# Syntheseproject.net
KiCad netlist of a schematic drawn in EasyEDA
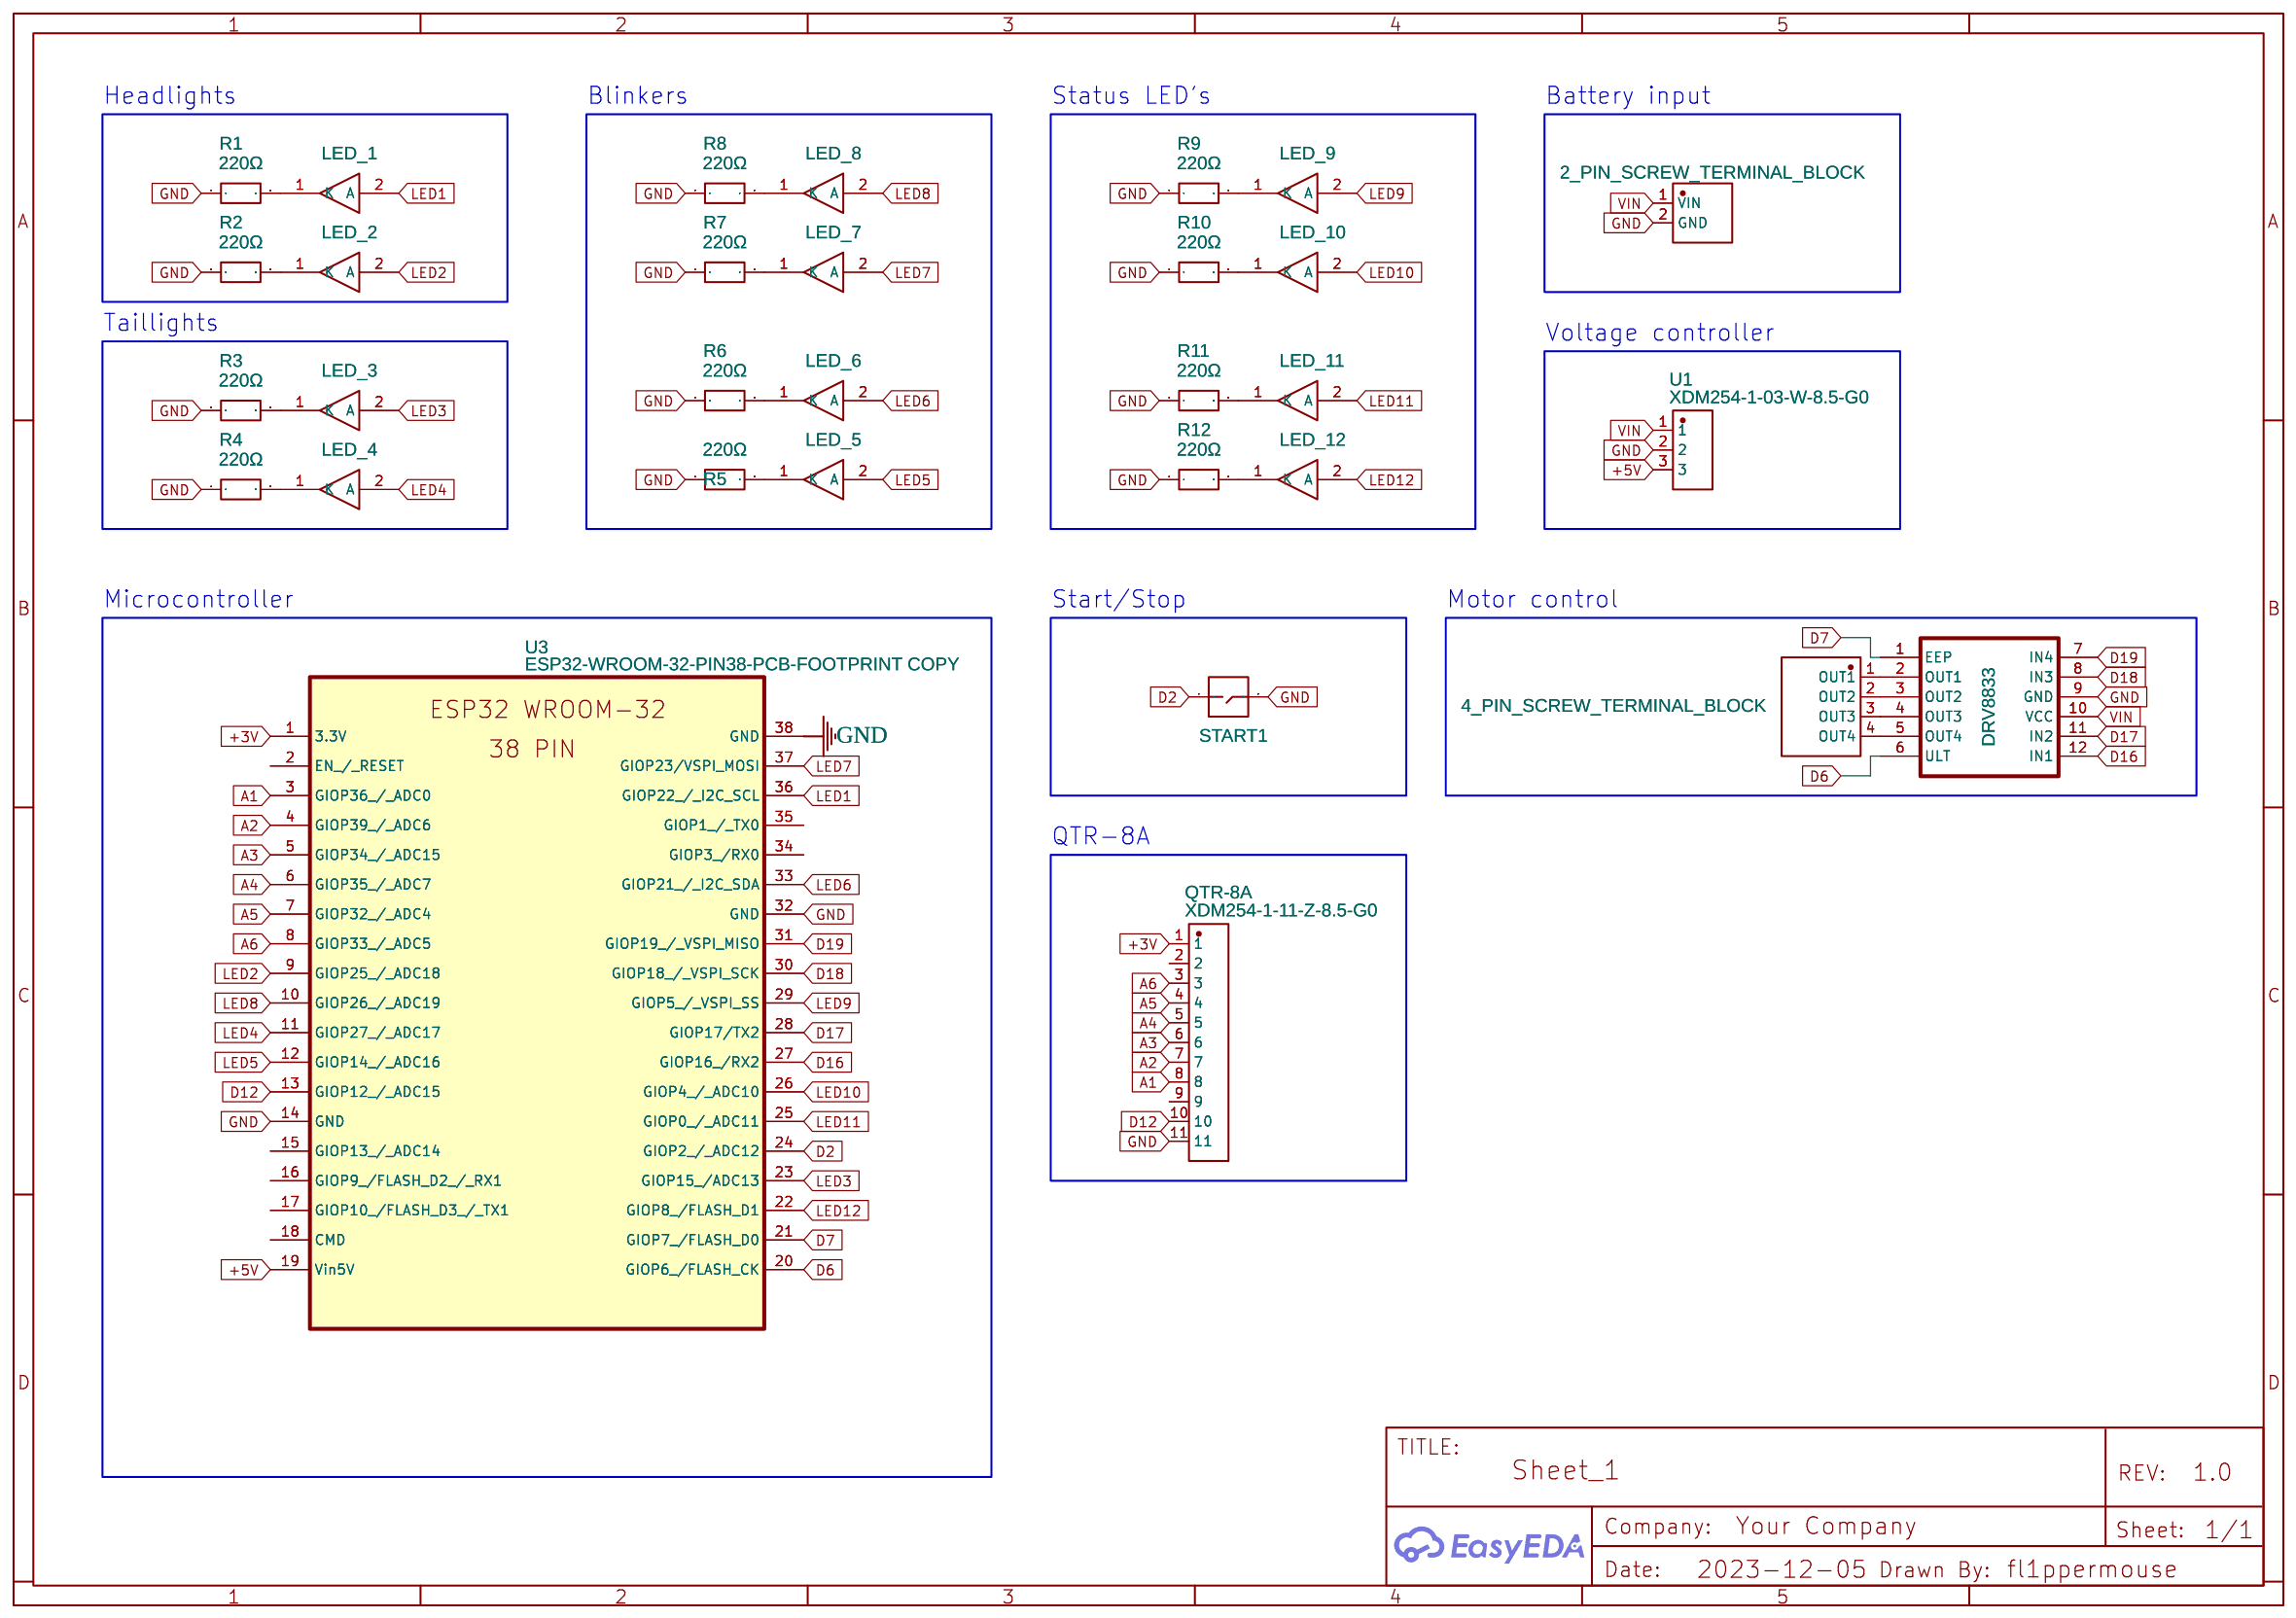
[diagram p0: schematic sheet]

(export (version "E")
  (design (tool "Eeschema 10.0.6"))
  (components
    (comp (ref "2_PIN_SCREW_TERMINAL_BLOCK")
      (value "2 Pin Screw Terminal Block Connector 2.54 mm")
      (libsource (lib "") (part "2 PIN SCREW TERMINAL BLOCK CONNECTOR 2.54 MM"))
    )
    (comp (ref "4_PIN_SCREW_TERMINAL_BLOCK")
      (value "4 PIN SCREW TERMINAL BLOCK CONNECTOR 2.54 MM")
      (libsource (lib "") (part "4 PIN SCREW TERMINAL BLOCK CONNECTOR 2.54 MM"))
    )
    (comp (ref "DRV8833") (value "DRV8833") (libsource (lib "") (part "DRV8833 12PIN")))
    (comp (ref "LED_1") (value "led 5 mm") (libsource (lib "") (part "led 5 mm")))
    (comp (ref "LED_2") (value "led 5 mm") (libsource (lib "") (part "led 5 mm")))
    (comp (ref "LED_3") (value "led 5 mm") (libsource (lib "") (part "led 5 mm")))
    (comp (ref "LED_4") (value "led 5 mm") (libsource (lib "") (part "led 5 mm")))
    (comp (ref "LED_5") (value "led 5 mm") (libsource (lib "") (part "led 5 mm")))
    (comp (ref "LED_6") (value "led 5 mm") (libsource (lib "") (part "led 5 mm")))
    (comp (ref "LED_7") (value "led 5 mm") (libsource (lib "") (part "led 5 mm")))
    (comp (ref "LED_8") (value "led 5 mm") (libsource (lib "") (part "led 5 mm")))
    (comp (ref "LED_9") (value "led 5 mm") (libsource (lib "") (part "led 5 mm")))
    (comp (ref "LED_10") (value "led 5 mm") (libsource (lib "") (part "led 5 mm")))
    (comp (ref "LED_11") (value "led 5 mm") (libsource (lib "") (part "led 5 mm")))
    (comp (ref "LED_12") (value "led 5 mm") (libsource (lib "") (part "led 5 mm")))
    (comp (ref "QTR-8A")
      (value "XDM254-1-11-Z-8.5-G0")
      (fields (field (name "Manufacturer") "XUNDA(讯答)"))
      (libsource (lib "") (part "XDM254-1-11-Z-8.5-G0"))
    )
    (comp (ref "R1")
      (value "220Ω")
      (libsource (lib "") (part "AXIAL RESISTOR 220 OHM - TH_BD2.3-L6.0-P10.00-D0.4"))
    )
    (comp (ref "R2")
      (value "220Ω")
      (libsource (lib "") (part "AXIAL RESISTOR 220 OHM - TH_BD2.3-L6.0-P10.00-D0.4"))
    )
    (comp (ref "R3")
      (value "220Ω")
      (libsource (lib "") (part "AXIAL RESISTOR 220 OHM - TH_BD2.3-L6.0-P10.00-D0.4"))
    )
    (comp (ref "R4")
      (value "220Ω")
      (libsource (lib "") (part "AXIAL RESISTOR 220 OHM - TH_BD2.3-L6.0-P10.00-D0.4"))
    )
    (comp (ref "R5")
      (value "220Ω")
      (libsource (lib "") (part "AXIAL RESISTOR 220 OHM - TH_BD2.3-L6.0-P10.00-D0.4"))
    )
    (comp (ref "R6")
      (value "220Ω")
      (libsource (lib "") (part "AXIAL RESISTOR 220 OHM - TH_BD2.3-L6.0-P10.00-D0.4"))
    )
    (comp (ref "R7")
      (value "220Ω")
      (libsource (lib "") (part "AXIAL RESISTOR 220 OHM - TH_BD2.3-L6.0-P10.00-D0.4"))
    )
    (comp (ref "R8")
      (value "220Ω")
      (libsource (lib "") (part "AXIAL RESISTOR 220 OHM - TH_BD2.3-L6.0-P10.00-D0.4"))
    )
    (comp (ref "R9")
      (value "220Ω")
      (libsource (lib "") (part "AXIAL RESISTOR 220 OHM - TH_BD2.3-L6.0-P10.00-D0.4"))
    )
    (comp (ref "R10")
      (value "220Ω")
      (libsource (lib "") (part "AXIAL RESISTOR 220 OHM - TH_BD2.3-L6.0-P10.00-D0.4"))
    )
    (comp (ref "R11")
      (value "220Ω")
      (libsource (lib "") (part "AXIAL RESISTOR 220 OHM - TH_BD2.3-L6.0-P10.00-D0.4"))
    )
    (comp (ref "R12")
      (value "220Ω")
      (libsource (lib "") (part "AXIAL RESISTOR 220 OHM - TH_BD2.3-L6.0-P10.00-D0.4"))
    )
    (comp (ref "START1") (value "start") (libsource (lib "") (part "Push Button")))
    (comp (ref "U1")
      (value "XDM254-1-03-W-8.5-G0")
      (fields (field (name "Manufacturer") "XUNDA(讯答)"))
      (libsource (lib "") (part "XDM254-1-03-W-8.5-G0"))
    )
    (comp (ref "U3")
      (value "ESP32-WROOM-32-PIN38-PCB-FOOTPRINT COPY")
      (fields
        (field (name "Manufacturer Part") "ESP32-WROOM-32")
        (field (name "Manufacturer") "Espressif Systems")
      )
      (libsource (lib "") (part "ESP32-WROOM-32-PIN38-PCB-FOOTPRINT COPY"))
    )
  )
  (nets
    (net (code "1") (name "+3V") (class "Default")
      (node (ref "QTR-8A") (pin "1") (pinfunction "1_1") (pintype "unspecified"))
      (node (ref "U3") (pin "1") (pinfunction "3.3V_1") (pintype "unspecified"))
    )
    (net (code "2") (name "+5V") (class "Default")
      (node (ref "U1") (pin "3") (pinfunction "3_3") (pintype "unspecified"))
      (node (ref "U3") (pin "19") (pinfunction "Vin5V_19") (pintype "unspecified"))
    )
    (net (code "3") (name "A1") (class "Default")
      (node (ref "QTR-8A") (pin "8") (pinfunction "8_8") (pintype "unspecified"))
      (node (ref "U3") (pin "3") (pinfunction "GIOP36_/_ADC0_3") (pintype "unspecified"))
    )
    (net (code "4") (name "A2") (class "Default")
      (node (ref "QTR-8A") (pin "7") (pinfunction "7_7") (pintype "unspecified"))
      (node (ref "U3") (pin "4") (pinfunction "GIOP39_/_ADC6_4") (pintype "unspecified"))
    )
    (net (code "5") (name "A3") (class "Default")
      (node (ref "QTR-8A") (pin "6") (pinfunction "6_6") (pintype "unspecified"))
      (node (ref "U3") (pin "5") (pinfunction "GIOP34_/_ADC15_5") (pintype "unspecified"))
    )
    (net (code "6") (name "A4") (class "Default")
      (node (ref "QTR-8A") (pin "5") (pinfunction "5_5") (pintype "unspecified"))
      (node (ref "U3") (pin "6") (pinfunction "GIOP35_/_ADC7_6") (pintype "unspecified"))
    )
    (net (code "7") (name "A5") (class "Default")
      (node (ref "QTR-8A") (pin "4") (pinfunction "4_4") (pintype "unspecified"))
      (node (ref "U3") (pin "7") (pinfunction "GIOP32_/_ADC4_7") (pintype "unspecified"))
    )
    (net (code "8") (name "A6") (class "Default")
      (node (ref "QTR-8A") (pin "3") (pinfunction "3_3") (pintype "unspecified"))
      (node (ref "U3") (pin "8") (pinfunction "GIOP33_/_ADC5_8") (pintype "unspecified"))
    )
    (net (code "9") (name "D2") (class "Default")
      (node (ref "START1") (pin "1") (pinfunction "1_1") (pintype "unspecified"))
      (node (ref "U3") (pin "24") (pinfunction "GIOP2_/_ADC12_24") (pintype "unspecified"))
    )
    (net (code "10") (name "D6") (class "Default")
      (node (ref "DRV8833") (pin "6") (pinfunction "ULT_6") (pintype "unspecified"))
      (node (ref "U3") (pin "20") (pinfunction "GIOP6_/FLASH_CK_20") (pintype "unspecified"))
    )
    (net (code "11") (name "D7") (class "Default")
      (node (ref "DRV8833") (pin "1") (pinfunction "EEP_1") (pintype "unspecified"))
      (node (ref "U3") (pin "21") (pinfunction "GIOP7_/FLASH_D0_21") (pintype "unspecified"))
    )
    (net (code "12") (name "D12") (class "Default")
      (node (ref "QTR-8A") (pin "10") (pinfunction "10_10") (pintype "unspecified"))
      (node (ref "U3") (pin "13") (pinfunction "GIOP12_/_ADC15_13") (pintype "unspecified"))
    )
    (net (code "13") (name "D16") (class "Default")
      (node (ref "DRV8833") (pin "12") (pinfunction "IN1_12") (pintype "unspecified"))
      (node (ref "U3") (pin "27") (pinfunction "GIOP16_/RX2_27") (pintype "unspecified"))
    )
    (net (code "14") (name "D17") (class "Default")
      (node (ref "DRV8833") (pin "11") (pinfunction "IN2_11") (pintype "unspecified"))
      (node (ref "U3") (pin "28") (pinfunction "GIOP17/TX2_28") (pintype "unspecified"))
    )
    (net (code "15") (name "D18") (class "Default")
      (node (ref "DRV8833") (pin "8") (pinfunction "IN3_8") (pintype "unspecified"))
      (node (ref "U3") (pin "30") (pinfunction "GIOP18_/_VSPI_SCK_30") (pintype "unspecified"))
    )
    (net (code "16") (name "D19") (class "Default")
      (node (ref "DRV8833") (pin "7") (pinfunction "IN4_7") (pintype "unspecified"))
      (node (ref "U3") (pin "31") (pinfunction "GIOP19_/_VSPI_MISO_31") (pintype "unspecified"))
    )
    (net (code "17") (name "GND") (class "Default")
      (node (ref "2_PIN_SCREW_TERMINAL_BLOCK") (pin "2") (pinfunction "GND_2") (pintype "unspecified"))
      (node (ref "DRV8833") (pin "9") (pinfunction "GND_9") (pintype "unspecified"))
      (node (ref "QTR-8A") (pin "11") (pinfunction "11_11") (pintype "unspecified"))
      (node (ref "R1") (pin "1") (pinfunction "1_1") (pintype "unspecified"))
      (node (ref "R10") (pin "1") (pinfunction "1_1") (pintype "unspecified"))
      (node (ref "R11") (pin "1") (pinfunction "1_1") (pintype "unspecified"))
      (node (ref "R12") (pin "1") (pinfunction "1_1") (pintype "unspecified"))
      (node (ref "R2") (pin "1") (pinfunction "1_1") (pintype "unspecified"))
      (node (ref "R3") (pin "1") (pinfunction "1_1") (pintype "unspecified"))
      (node (ref "R4") (pin "1") (pinfunction "1_1") (pintype "unspecified"))
      (node (ref "R5") (pin "1") (pinfunction "1_1") (pintype "unspecified"))
      (node (ref "R6") (pin "1") (pinfunction "1_1") (pintype "unspecified"))
      (node (ref "R7") (pin "1") (pinfunction "1_1") (pintype "unspecified"))
      (node (ref "R8") (pin "1") (pinfunction "1_1") (pintype "unspecified"))
      (node (ref "R9") (pin "1") (pinfunction "1_1") (pintype "unspecified"))
      (node (ref "START1") (pin "2") (pinfunction "2_2") (pintype "unspecified"))
      (node (ref "U1") (pin "2") (pinfunction "2_2") (pintype "unspecified"))
      (node (ref "U3") (pin "14") (pinfunction "GND_14") (pintype "unspecified"))
      (node (ref "U3") (pin "32") (pinfunction "GND_32") (pintype "unspecified"))
      (node (ref "U3") (pin "38") (pinfunction "GND_38") (pintype "unspecified"))
    )
    (net (code "18") (name "LED1") (class "Default")
      (node (ref "LED_1") (pin "2") (pinfunction "A_2") (pintype "unspecified"))
      (node (ref "U3") (pin "36") (pinfunction "GIOP22_/_I2C_SCL_36") (pintype "unspecified"))
    )
    (net (code "19") (name "LED2") (class "Default")
      (node (ref "LED_2") (pin "2") (pinfunction "A_2") (pintype "unspecified"))
      (node (ref "U3") (pin "9") (pinfunction "GIOP25_/_ADC18_9") (pintype "unspecified"))
    )
    (net (code "20") (name "LED3") (class "Default")
      (node (ref "LED_3") (pin "2") (pinfunction "A_2") (pintype "unspecified"))
      (node (ref "U3") (pin "23") (pinfunction "GIOP15_/ADC13_23") (pintype "unspecified"))
    )
    (net (code "21") (name "LED4") (class "Default")
      (node (ref "LED_4") (pin "2") (pinfunction "A_2") (pintype "unspecified"))
      (node (ref "U3") (pin "11") (pinfunction "GIOP27_/_ADC17_11") (pintype "unspecified"))
    )
    (net (code "22") (name "LED5") (class "Default")
      (node (ref "LED_5") (pin "2") (pinfunction "A_2") (pintype "unspecified"))
      (node (ref "U3") (pin "12") (pinfunction "GIOP14_/_ADC16_12") (pintype "unspecified"))
    )
    (net (code "23") (name "LED6") (class "Default")
      (node (ref "LED_6") (pin "2") (pinfunction "A_2") (pintype "unspecified"))
      (node (ref "U3") (pin "33") (pinfunction "GIOP21_/_I2C_SDA_33") (pintype "unspecified"))
    )
    (net (code "24") (name "LED7") (class "Default")
      (node (ref "LED_7") (pin "2") (pinfunction "A_2") (pintype "unspecified"))
      (node (ref "U3") (pin "37") (pinfunction "GIOP23/VSPI_MOSI_37") (pintype "unspecified"))
    )
    (net (code "25") (name "LED8") (class "Default")
      (node (ref "LED_8") (pin "2") (pinfunction "A_2") (pintype "unspecified"))
      (node (ref "U3") (pin "10") (pinfunction "GIOP26_/_ADC19_10") (pintype "unspecified"))
    )
    (net (code "26") (name "LED9") (class "Default")
      (node (ref "LED_9") (pin "2") (pinfunction "A_2") (pintype "unspecified"))
      (node (ref "U3") (pin "29") (pinfunction "GIOP5_/_VSPI_SS_29") (pintype "unspecified"))
    )
    (net (code "27") (name "LED10") (class "Default")
      (node (ref "LED_10") (pin "2") (pinfunction "A_2") (pintype "unspecified"))
      (node (ref "U3") (pin "26") (pinfunction "GIOP4_/_ADC10_26") (pintype "unspecified"))
    )
    (net (code "28") (name "LED11") (class "Default")
      (node (ref "LED_11") (pin "2") (pinfunction "A_2") (pintype "unspecified"))
      (node (ref "U3") (pin "25") (pinfunction "GIOP0_/_ADC11_25") (pintype "unspecified"))
    )
    (net (code "29") (name "LED12") (class "Default")
      (node (ref "LED_12") (pin "2") (pinfunction "A_2") (pintype "unspecified"))
      (node (ref "U3") (pin "22") (pinfunction "GIOP8_/FLASH_D1_22") (pintype "unspecified"))
    )
    (net (code "30") (name "Net-(4_PIN_SCREW_TERMINAL_BLOCK-OUT1)") (class "Default")
      (node (ref "4_PIN_SCREW_TERMINAL_BLOCK") (pin "1") (pinfunction "OUT1_1") (pintype "unspecified"))
      (node (ref "DRV8833") (pin "2") (pinfunction "OUT1_2") (pintype "unspecified"))
    )
    (net (code "31") (name "Net-(4_PIN_SCREW_TERMINAL_BLOCK-OUT2)") (class "Default")
      (node (ref "4_PIN_SCREW_TERMINAL_BLOCK") (pin "2") (pinfunction "OUT2_2") (pintype "unspecified"))
      (node (ref "DRV8833") (pin "3") (pinfunction "OUT2_3") (pintype "unspecified"))
    )
    (net (code "32") (name "Net-(4_PIN_SCREW_TERMINAL_BLOCK-OUT3)") (class "Default")
      (node (ref "4_PIN_SCREW_TERMINAL_BLOCK") (pin "3") (pinfunction "OUT3_3") (pintype "unspecified"))
      (node (ref "DRV8833") (pin "4") (pinfunction "OUT3_4") (pintype "unspecified"))
    )
    (net (code "33") (name "Net-(4_PIN_SCREW_TERMINAL_BLOCK-OUT4)") (class "Default")
      (node (ref "4_PIN_SCREW_TERMINAL_BLOCK") (pin "4") (pinfunction "OUT4_4") (pintype "unspecified"))
      (node (ref "DRV8833") (pin "5") (pinfunction "OUT4_5") (pintype "unspecified"))
    )
    (net (code "34") (name "Net-(LED_1-K)") (class "Default")
      (node (ref "LED_1") (pin "1") (pinfunction "K_1") (pintype "unspecified"))
      (node (ref "R1") (pin "2") (pinfunction "2_2") (pintype "unspecified"))
    )
    (net (code "35") (name "Net-(LED_2-K)") (class "Default")
      (node (ref "LED_2") (pin "1") (pinfunction "K_1") (pintype "unspecified"))
      (node (ref "R2") (pin "2") (pinfunction "2_2") (pintype "unspecified"))
    )
    (net (code "36") (name "Net-(LED_3-K)") (class "Default")
      (node (ref "LED_3") (pin "1") (pinfunction "K_1") (pintype "unspecified"))
      (node (ref "R3") (pin "2") (pinfunction "2_2") (pintype "unspecified"))
    )
    (net (code "37") (name "Net-(LED_4-K)") (class "Default")
      (node (ref "LED_4") (pin "1") (pinfunction "K_1") (pintype "unspecified"))
      (node (ref "R4") (pin "2") (pinfunction "2_2") (pintype "unspecified"))
    )
    (net (code "38") (name "Net-(LED_5-K)") (class "Default")
      (node (ref "LED_5") (pin "1") (pinfunction "K_1") (pintype "unspecified"))
      (node (ref "R5") (pin "2") (pinfunction "2_2") (pintype "unspecified"))
    )
    (net (code "39") (name "Net-(LED_6-K)") (class "Default")
      (node (ref "LED_6") (pin "1") (pinfunction "K_1") (pintype "unspecified"))
      (node (ref "R6") (pin "2") (pinfunction "2_2") (pintype "unspecified"))
    )
    (net (code "40") (name "Net-(LED_7-K)") (class "Default")
      (node (ref "LED_7") (pin "1") (pinfunction "K_1") (pintype "unspecified"))
      (node (ref "R7") (pin "2") (pinfunction "2_2") (pintype "unspecified"))
    )
    (net (code "41") (name "Net-(LED_8-K)") (class "Default")
      (node (ref "LED_8") (pin "1") (pinfunction "K_1") (pintype "unspecified"))
      (node (ref "R8") (pin "2") (pinfunction "2_2") (pintype "unspecified"))
    )
    (net (code "42") (name "Net-(LED_9-K)") (class "Default")
      (node (ref "LED_9") (pin "1") (pinfunction "K_1") (pintype "unspecified"))
      (node (ref "R9") (pin "2") (pinfunction "2_2") (pintype "unspecified"))
    )
    (net (code "43") (name "Net-(LED_10-K)") (class "Default")
      (node (ref "LED_10") (pin "1") (pinfunction "K_1") (pintype "unspecified"))
      (node (ref "R10") (pin "2") (pinfunction "2_2") (pintype "unspecified"))
    )
    (net (code "44") (name "Net-(LED_11-K)") (class "Default")
      (node (ref "LED_11") (pin "1") (pinfunction "K_1") (pintype "unspecified"))
      (node (ref "R11") (pin "2") (pinfunction "2_2") (pintype "unspecified"))
    )
    (net (code "45") (name "Net-(LED_12-K)") (class "Default")
      (node (ref "LED_12") (pin "1") (pinfunction "K_1") (pintype "unspecified"))
      (node (ref "R12") (pin "2") (pinfunction "2_2") (pintype "unspecified"))
    )
    (net (code "46") (name "VIN") (class "Default")
      (node (ref "2_PIN_SCREW_TERMINAL_BLOCK") (pin "1") (pinfunction "VIN_1") (pintype "unspecified"))
      (node (ref "DRV8833") (pin "10") (pinfunction "VCC_10") (pintype "unspecified"))
      (node (ref "U1") (pin "1") (pinfunction "1_1") (pintype "unspecified"))
    )
    (net (code "47") (name "unconnected-(QTR-8A-Pad2)") (class "Default")
      (node (ref "QTR-8A") (pin "2") (pinfunction "2_2") (pintype "unspecified"))
    )
    (net (code "48") (name "unconnected-(QTR-8A-Pad9)") (class "Default")
      (node (ref "QTR-8A") (pin "9") (pinfunction "9_9") (pintype "unspecified"))
    )
    (net (code "49") (name "unconnected-(U3-CMD-Pad18)") (class "Default")
      (node (ref "U3") (pin "18") (pinfunction "CMD_18") (pintype "unspecified"))
    )
    (net (code "50") (name "unconnected-(U3-EN_{slash}_RESET-Pad2)") (class "Default")
      (node (ref "U3") (pin "2") (pinfunction "EN_/_RESET_2") (pintype "unspecified"))
    )
    (net (code "51") (name "unconnected-(U3-GIOP1_{slash}_TX0-Pad35)") (class "Default")
      (node (ref "U3") (pin "35") (pinfunction "GIOP1_/_TX0_35") (pintype "unspecified"))
    )
    (net (code "52") (name "unconnected-(U3-GIOP3_{slash}RX0-Pad34)") (class "Default")
      (node (ref "U3") (pin "34") (pinfunction "GIOP3_/RX0_34") (pintype "unspecified"))
    )
    (net (code "53") (name "unconnected-(U3-GIOP9_{slash}FLASH_D2_{slash}_RX1-Pad16)") (class "Default")
      (node (ref "U3") (pin "16") (pinfunction "GIOP9_/FLASH_D2_/_RX1_16") (pintype "unspecified"))
    )
    (net (code "54") (name "unconnected-(U3-GIOP10_{slash}FLASH_D3_{slash}_TX1-Pad17)") (class "Default")
      (node (ref "U3") (pin "17") (pinfunction "GIOP10_/FLASH_D3_/_TX1_17") (pintype "unspecified"))
    )
    (net (code "55") (name "unconnected-(U3-GIOP13_{slash}_ADC14-Pad15)") (class "Default")
      (node (ref "U3") (pin "15") (pinfunction "GIOP13_/_ADC14_15") (pintype "unspecified"))
    )
  )
)
